# 0_powerv4.net
KiCad netlist of a schematic drawn in Altium Designer
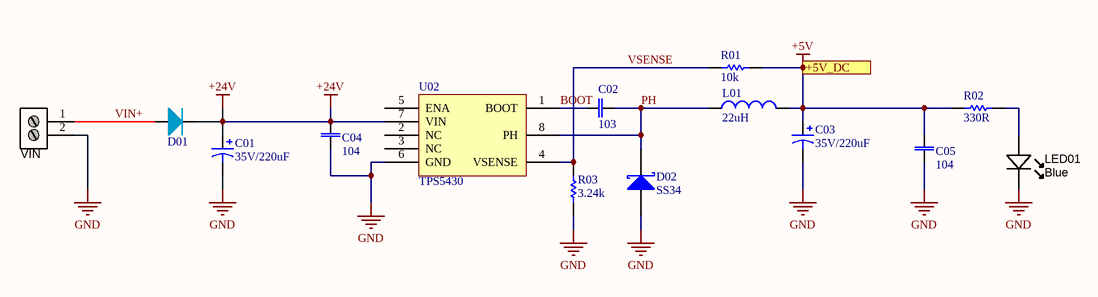
[diagram p0: 0.powerv4.SchDoc]

(export (version "E")
  (design (tool "Eeschema 10.0.6"))
  (components
    (comp (ref "C01")
      (value "35V/220uF")
      (footprint "CAPE3.5-5.0MM_Rad_10x14mm")
      (fields (field (name "Comment") "Tụ nhôm cắm35V/220uF"))
      (libsource (lib "Tuan") (part "Cap"))
    )
    (comp (ref "C02")
      (value "103")
      (footprint "swatpcblib:CAP 0805")
      (description "Capacitor non polarized")
      (fields (field (name "Comment") "Tụ điện dán 0805103"))
      (libsource (lib "swatpcblib") (part "CAP NP"))
    )
    (comp (ref "C03")
      (value "35V/220uF")
      (footprint "CAPE3.5-5.0MM_Rad_10x14mm")
      (fields (field (name "Comment") "Tụ nhôm cắm35V/220uF"))
      (libsource (lib "Tuan") (part "Cap"))
    )
    (comp (ref "C04")
      (value "104")
      (footprint "swatpcblib:CAP 0805")
      (description "Capacitor non polarized")
      (fields (field (name "Comment") "Tụ điện dán 0805104"))
      (libsource (lib "swatpcblib") (part "CAP NP"))
    )
    (comp (ref "C05")
      (value "104")
      (footprint "swatpcblib:CAP 0805")
      (description "Capacitor non polarized")
      (fields (field (name "Comment") "Tụ điện dán 0805104"))
      (libsource (lib "swatpcblib") (part "CAP NP"))
    )
    (comp (ref "D01")
      (value "Đi ốt dán M7chân DO-214AB")
      (footprint "DO-214AA")
      (libsource (lib "Tuan") (part "Diode"))
    )
    (comp (ref "D02") (value "SS34") (footprint "SMD diode") (libsource (lib "Tuan") (part "Diode Schottky")))
    (comp (ref "L01")
      (value "22uH")
      (footprint "Inductor 12x12x6")
      (fields (field (name "Comment") "Cuộn cảm dán22uH"))
      (libsource (lib "swatpcblib") (part "Inductor"))
    )
    (comp (ref "LED01")
      (value "Blue")
      (footprint "LED-0805-K")
      (description "LED 0805 SMD Blue 100mcd 470nm")
      (fields (field (name "COLOR") "Blue"))
      (libsource (lib "PBL - Light Sources") (part "LED_SMD_Blue_0805_100mcd"))
    )
    (comp (ref "R01")
      (value "10k")
      (footprint "swatpcblib:RES 0805")
      (description "Resistor")
      (fields (field (name "Comment") "Điện trở dán 080510k"))
      (libsource (lib "swatpcblib") (part "Res"))
    )
    (comp (ref "R02")
      (value "330R")
      (footprint "swatpcblib:RES 0805")
      (description "Resistor")
      (fields (field (name "Comment") "Điện trở dán 0805330R"))
      (libsource (lib "swatpcblib") (part "Res"))
    )
    (comp (ref "R03")
      (value "3.24k")
      (footprint "swatpcblib:RES 0805")
      (description "Resistor")
      (fields (field (name "Comment") "Điện trở dán 08053.24k"))
      (libsource (lib "swatpcblib") (part "Res"))
    )
    (comp (ref "U02") (value "TPS5430") (footprint "SOIC 8") (libsource (lib "Tuan") (part "TPS5430")))
    (comp (ref "VIN")
      (value "Giắc xanh 5.08mm")
      (footprint "2P_PCB1")
      (description "Terminal Block Screw Type THT 2-Position 3.81mm pitch")
      (libsource (lib "PBL - Connectors") (part "2P_ScrewTerm_90S_3.81MM"))
    )
  )
  (nets
    (net (code "1") (name "+5V") (class "Default")
      (node (ref "C03") (pin "1") (pinfunction "1_1") (pintype "passive"))
      (node (ref "C05") (pin "2") (pinfunction "2_2") (pintype "passive"))
      (node (ref "L01") (pin "2") (pinfunction "2_2") (pintype "passive"))
      (node (ref "R01") (pin "1") (pinfunction "1_1") (pintype "passive"))
      (node (ref "R02") (pin "2") (pinfunction "2_2") (pintype "passive"))
    )
    (net (code "2") (name "+24V") (class "Default")
      (node (ref "C01") (pin "1") (pinfunction "1_1") (pintype "passive"))
      (node (ref "C04") (pin "2") (pinfunction "2_2") (pintype "passive"))
      (node (ref "D01") (pin "2") (pinfunction "K_2") (pintype "passive"))
      (node (ref "U02") (pin "7") (pinfunction "VIN_7") (pintype "power_in"))
    )
    (net (code "3") (name "/BOOT") (class "Default")
      (node (ref "C02") (pin "1") (pinfunction "1_1") (pintype "passive"))
      (node (ref "U02") (pin "1") (pinfunction "BOOT_1") (pintype "power_in"))
    )
    (net (code "4") (name "/PH") (class "Default")
      (node (ref "C02") (pin "2") (pinfunction "2_2") (pintype "passive"))
      (node (ref "D02") (pin "2") (pinfunction "K_2") (pintype "passive"))
      (node (ref "L01") (pin "1") (pinfunction "1_1") (pintype "passive"))
      (node (ref "U02") (pin "8") (pinfunction "PH_8") (pintype "power_in"))
    )
    (net (code "5") (name "/VIN+") (class "Default")
      (node (ref "D01") (pin "1") (pinfunction "A_1") (pintype "passive"))
      (node (ref "VIN") (pin "1") (pinfunction "1_1") (pintype "passive"))
    )
    (net (code "6") (name "/VSENSE") (class "Default")
      (node (ref "R01") (pin "2") (pinfunction "2_2") (pintype "passive"))
      (node (ref "R03") (pin "2") (pinfunction "2_2") (pintype "passive"))
      (node (ref "U02") (pin "4") (pinfunction "VSENSE_4") (pintype "power_in"))
    )
    (net (code "7") (name "GND") (class "Default")
      (node (ref "C01") (pin "2") (pinfunction "2_2") (pintype "passive"))
      (node (ref "C03") (pin "2") (pinfunction "2_2") (pintype "passive"))
      (node (ref "C04") (pin "1") (pinfunction "1_1") (pintype "passive"))
      (node (ref "C05") (pin "1") (pinfunction "1_1") (pintype "passive"))
      (node (ref "D02") (pin "1") (pinfunction "A_1") (pintype "passive"))
      (node (ref "LED01") (pin "K") (pinfunction "K_K") (pintype "passive"))
      (node (ref "R03") (pin "1") (pinfunction "1_1") (pintype "passive"))
      (node (ref "U02") (pin "6") (pinfunction "GND_6") (pintype "power_in"))
      (node (ref "VIN") (pin "2") (pinfunction "2_2") (pintype "passive"))
    )
    (net (code "8") (name "Net-(LED01-PadA)") (class "Default")
      (node (ref "LED01") (pin "A") (pinfunction "A_A") (pintype "passive"))
      (node (ref "R02") (pin "1") (pinfunction "1_1") (pintype "passive"))
    )
    (net (code "9") (name "unconnected-(U02-ENA-Pad5)") (class "Default")
      (node (ref "U02") (pin "5") (pinfunction "ENA_5") (pintype "power_in"))
    )
    (net (code "10") (name "unconnected-(U02-NC-Pad2)") (class "Default")
      (node (ref "U02") (pin "2") (pinfunction "NC_2") (pintype "power_in"))
    )
    (net (code "11") (name "unconnected-(U02-NC-Pad3)") (class "Default")
      (node (ref "U02") (pin "3") (pinfunction "NC_3") (pintype "power_in"))
    )
  )
)
